# LIS3DHTR.net
KiCad netlist of a schematic drawn in EAGLE
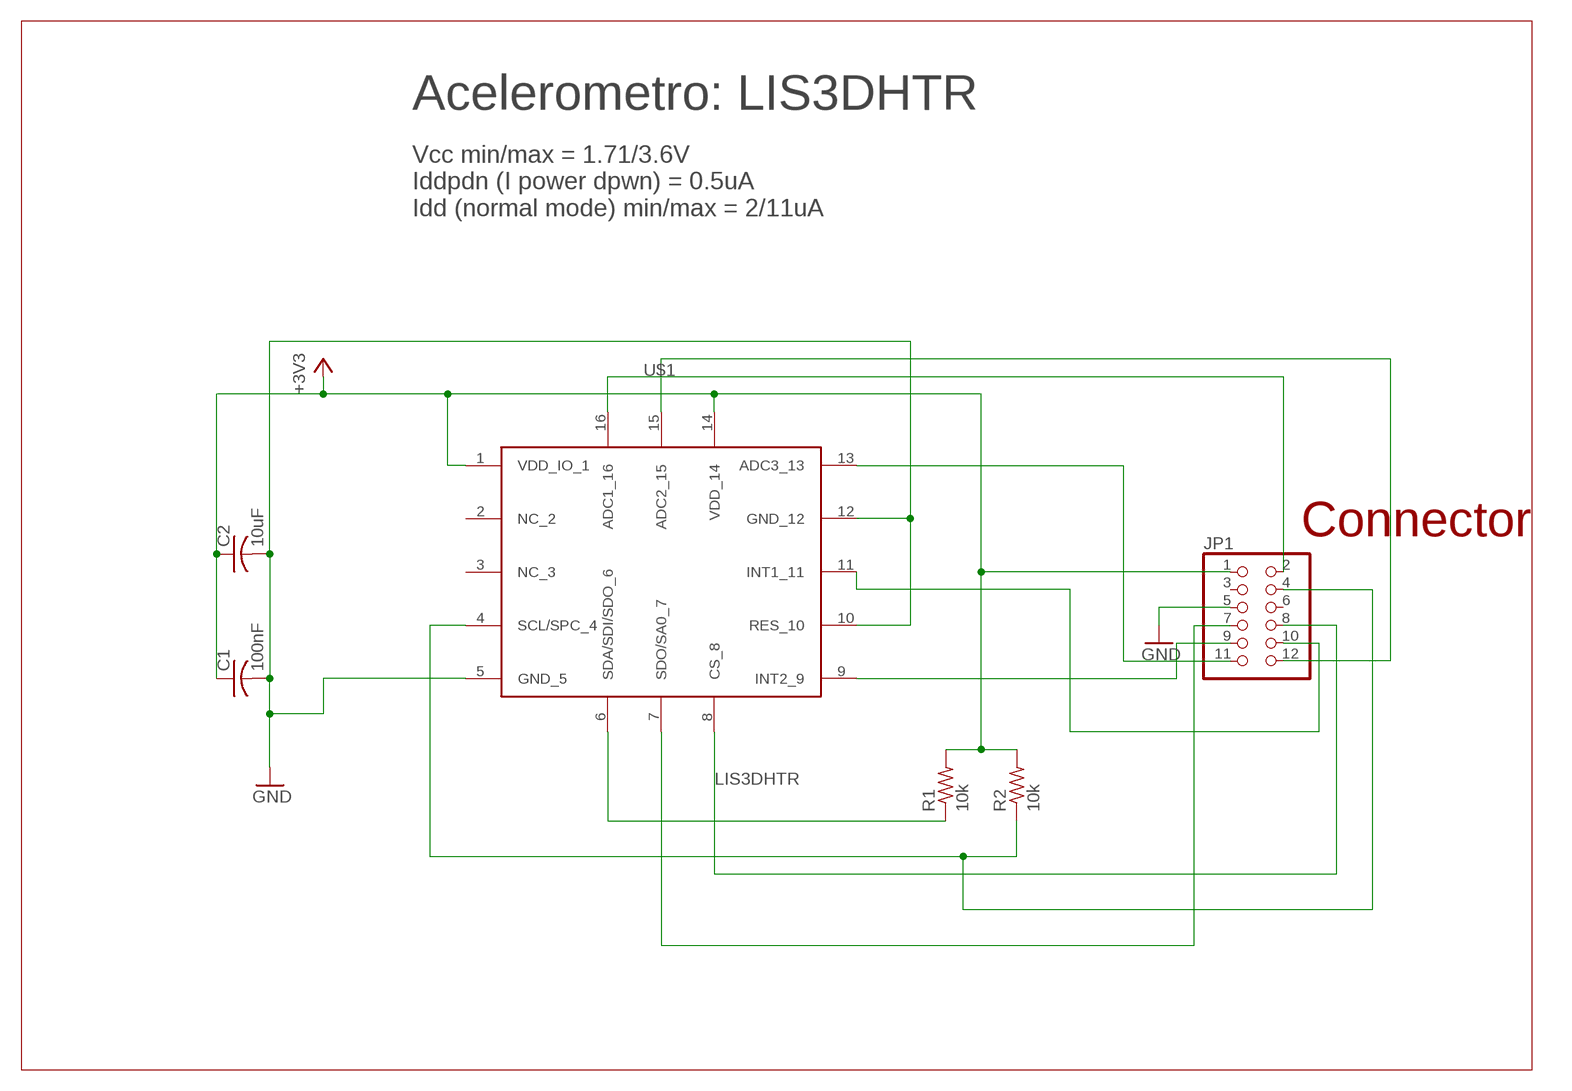
[diagram p0: schematic, sheet 1]

(export (version "E")
  (design (tool "Eeschema 10.0.6"))
  (components
    (comp (ref "C1")
      (value "100nF")
      (footprint "eagle-import:C0805")
      (fields (field (name "PARTNO") "GCM21BR72A104KA37L"))
      (libsource (lib "eagle-import") (part "C-USC0805"))
    )
    (comp (ref "C2")
      (value "10uF")
      (footprint "eagle-import:C0805")
      (fields (field (name "PARTNO") "EDK106M035A9BAA"))
      (libsource (lib "eagle-import") (part "C-USC0805"))
    )
    (comp (ref "JP1")
      (value "PINHD-2X6/90")
      (footprint "eagle-import:2X06_90")
      (libsource (lib "eagle-import") (part "PINHD-2X6/90"))
    )
    (comp (ref "R1")
      (value "10k")
      (footprint "eagle-import:R0805")
      (fields (field (name "PARTNO") "RC0805FR-0710KL"))
      (libsource (lib "eagle-import") (part "R-US_R0805"))
    )
    (comp (ref "R2")
      (value "10k")
      (footprint "eagle-import:R0805")
      (fields (field (name "PARTNO") "RC0805FR-0710KL"))
      (libsource (lib "eagle-import") (part "R-US_R0805"))
    )
    (comp (ref "U$1")
      (value "LIS3DHTR")
      (footprint "eagle-import:LGA-16-3X3")
      (libsource (lib "eagle-import") (part "LIS3DHTR"))
    )
  )
  (nets
    (net (code "1") (name "+3V3") (class "Default")
      (node (ref "C1") (pin "1") (pinfunction "1_1") (pintype "passive"))
      (node (ref "C2") (pin "1") (pinfunction "1_1") (pintype "passive"))
      (node (ref "JP1") (pin "1") (pinfunction "1_1") (pintype "passive"))
      (node (ref "R1") (pin "2") (pinfunction "2_2") (pintype "passive"))
      (node (ref "R2") (pin "2") (pinfunction "2_2") (pintype "passive"))
      (node (ref "U$1") (pin "1") (pinfunction "VDD_IO_1_1") (pintype "power_in"))
      (node (ref "U$1") (pin "14") (pinfunction "VDD_14_14") (pintype "power_in"))
    )
    (net (code "2") (name "GND") (class "Default")
      (node (ref "C1") (pin "2") (pinfunction "2_2") (pintype "passive"))
      (node (ref "C2") (pin "2") (pinfunction "2_2") (pintype "passive"))
      (node (ref "JP1") (pin "5") (pinfunction "5_5") (pintype "passive"))
      (node (ref "U$1") (pin "10") (pinfunction "RES_10_10") (pintype "input"))
      (node (ref "U$1") (pin "12") (pinfunction "GND_12_12") (pintype "power_in"))
      (node (ref "U$1") (pin "5") (pinfunction "GND_5_5") (pintype "power_in"))
    )
    (net (code "3") (name "Net-(U$1-ADC1_16)") (class "Default")
      (node (ref "JP1") (pin "2") (pinfunction "2_2") (pintype "passive"))
      (node (ref "U$1") (pin "16") (pinfunction "ADC1_16_16") (pintype "output"))
    )
    (net (code "4") (name "Net-(U$1-ADC2_15)") (class "Default")
      (node (ref "JP1") (pin "12") (pinfunction "12_12") (pintype "passive"))
      (node (ref "U$1") (pin "15") (pinfunction "ADC2_15_15") (pintype "output"))
    )
    (net (code "5") (name "Net-(U$1-ADC3_13)") (class "Default")
      (node (ref "JP1") (pin "11") (pinfunction "11_11") (pintype "passive"))
      (node (ref "U$1") (pin "13") (pinfunction "ADC3_13_13") (pintype "output"))
    )
    (net (code "6") (name "Net-(U$1-CS_8)") (class "Default")
      (node (ref "JP1") (pin "8") (pinfunction "8_8") (pintype "passive"))
      (node (ref "U$1") (pin "8") (pinfunction "CS_8_8") (pintype "input"))
    )
    (net (code "7") (name "Net-(U$1-INT1_11)") (class "Default")
      (node (ref "JP1") (pin "10") (pinfunction "10_10") (pintype "passive"))
      (node (ref "U$1") (pin "11") (pinfunction "INT1_11_11") (pintype "output"))
    )
    (net (code "8") (name "Net-(U$1-INT2_9)") (class "Default")
      (node (ref "JP1") (pin "9") (pinfunction "9_9") (pintype "passive"))
      (node (ref "U$1") (pin "9") (pinfunction "INT2_9_9") (pintype "output"))
    )
    (net (code "9") (name "Net-(U$1-SCL{slash}SPC_4)") (class "Default")
      (node (ref "JP1") (pin "4") (pinfunction "4_4") (pintype "passive"))
      (node (ref "R2") (pin "1") (pinfunction "1_1") (pintype "passive"))
      (node (ref "U$1") (pin "4") (pinfunction "SCL/SPC_4_4") (pintype "input"))
    )
    (net (code "10") (name "Net-(U$1-SDA{slash}SDI{slash}SDO_6)") (class "Default")
      (node (ref "R1") (pin "1") (pinfunction "1_1") (pintype "passive"))
      (node (ref "U$1") (pin "6") (pinfunction "SDA/SDI/SDO_6_6") (pintype "output"))
    )
    (net (code "11") (name "Net-(U$1-SDO{slash}SA0_7)") (class "Default")
      (node (ref "JP1") (pin "7") (pinfunction "7_7") (pintype "passive"))
      (node (ref "U$1") (pin "7") (pinfunction "SDO/SA0_7_7") (pintype "output"))
    )
    (net (code "12") (name "unconnected-(JP1-Pad3)") (class "Default")
      (node (ref "JP1") (pin "3") (pinfunction "3_3") (pintype "passive"))
    )
    (net (code "13") (name "unconnected-(JP1-Pad6)") (class "Default")
      (node (ref "JP1") (pin "6") (pinfunction "6_6") (pintype "passive"))
    )
    (net (code "14") (name "unconnected-(U$1-NC_2-Pad2)") (class "Default")
      (node (ref "U$1") (pin "2") (pinfunction "NC_2_2") (pintype "no_connect"))
    )
    (net (code "15") (name "unconnected-(U$1-NC_3-Pad3)") (class "Default")
      (node (ref "U$1") (pin "3") (pinfunction "NC_3_3") (pintype "no_connect"))
    )
  )
)
